# stepperDriver.net
KiCad netlist of a schematic drawn in Altium Designer
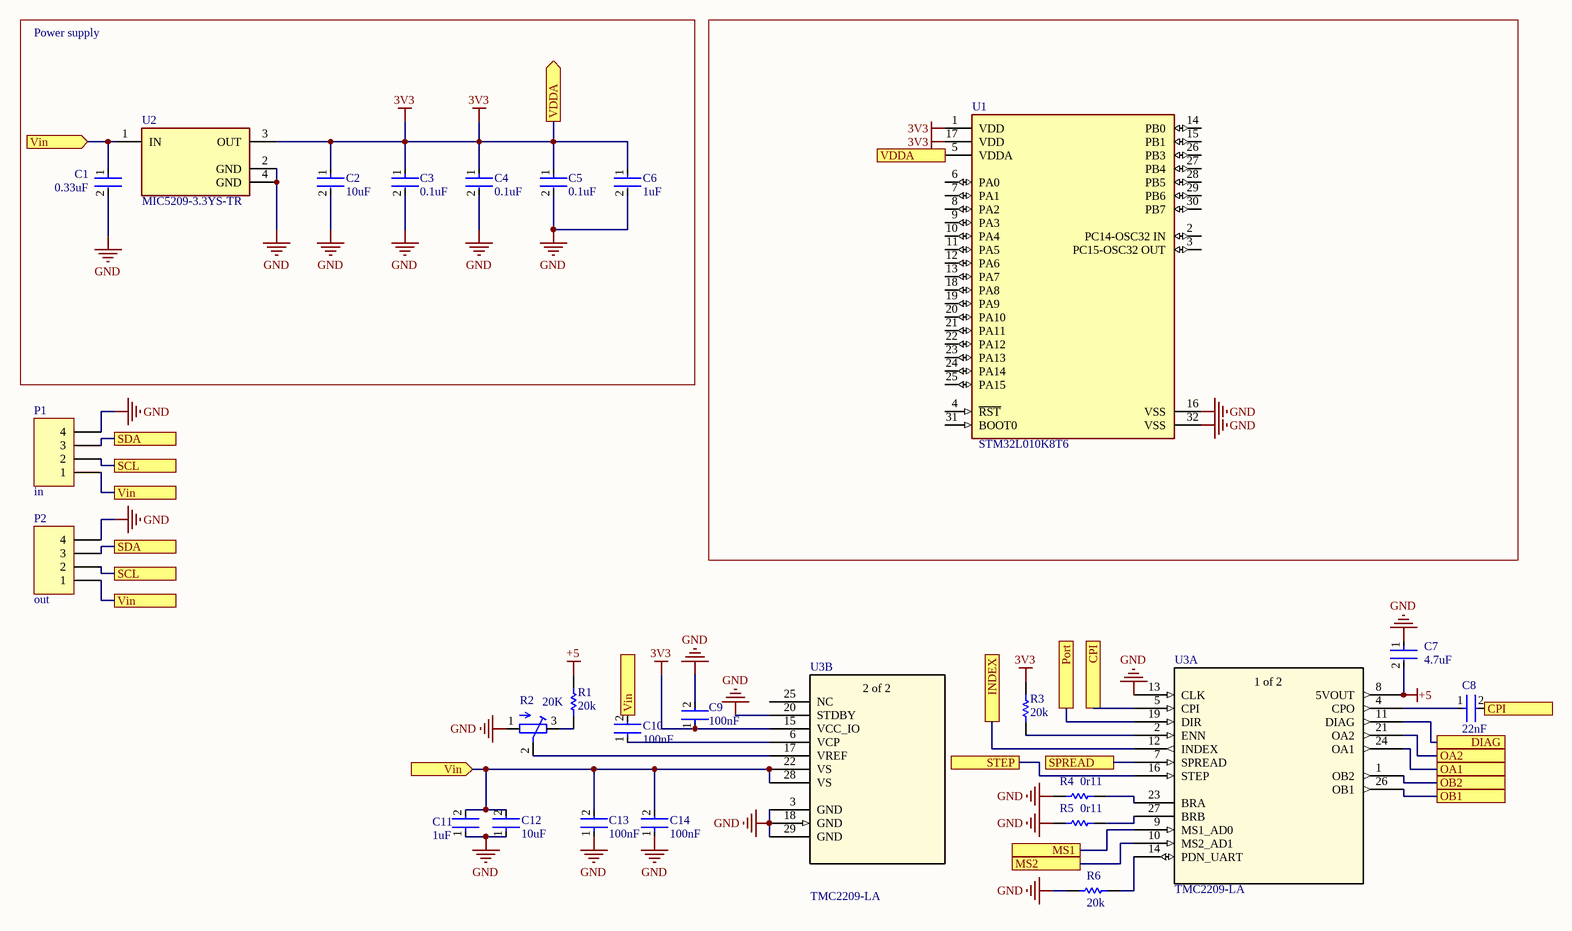
[diagram p0: stepperDriver.SchDoc]

(export (version "E")
  (design (tool "Eeschema 10.0.6"))
  (components
    (comp (ref "C1")
      (value "0.33uF")
      (footprint "FP-CL31-IPC_C")
      (description "Cap Ceramic 330pF 50V C0G ±5% SMD 1206 +125°C Embossed T/R")
      (fields (field (name "VOLTAGE") "50V") (field (name "TOLERANCE") "5%"))
      (libsource (lib "Altium Content Vault") (part "b4654b650e69147ec39a6b967a45e02"))
    )
    (comp (ref "C2")
      (value "10uF")
      (footprint "FP-CL31-IPC_A")
      (description "Cap Ceramic 10uF 16V X5R ±10% SMD 1206 +85°C Embossed T/R")
      (fields (field (name "VOLTAGE") "16V") (field (name "TOLERANCE") "10%"))
      (libsource (lib "Altium Content Vault") (part "b4654b650e69147ec39a6b967a45e02"))
    )
    (comp (ref "C3")
      (value "0.1uF")
      (footprint "FP-CGA5L-MFG")
      (description "CAP CER 0.1UF 50V C0G 1206")
      (fields
        (field (name "OCTOPART") "https://octopart.com/cga5l2c0g1h104j160aa-tdk-26014808")
        (field (name "MANUFACTURER") "TDK")
      )
      (libsource (lib "Altium Content Vault") (part "02cd4be3c70576c341d710602a673aa"))
    )
    (comp (ref "C4")
      (value "0.1uF")
      (footprint "FP-CGA5L-MFG")
      (description "CAP CER 0.1UF 50V C0G 1206")
      (fields
        (field (name "OCTOPART") "https://octopart.com/cga5l2c0g1h104j160aa-tdk-26014808")
        (field (name "MANUFACTURER") "TDK")
      )
      (libsource (lib "Altium Content Vault") (part "02cd4be3c70576c341d710602a673aa"))
    )
    (comp (ref "C5")
      (value "0.1uF")
      (footprint "FP-CGA5L-MFG")
      (description "CAP CER 0.1UF 50V C0G 1206")
      (fields
        (field (name "OCTOPART") "https://octopart.com/cga5l2c0g1h104j160aa-tdk-26014808")
        (field (name "MANUFACTURER") "TDK")
      )
      (libsource (lib "Altium Content Vault") (part "02cd4be3c70576c341d710602a673aa"))
    )
    (comp (ref "C6")
      (value "1uF")
      (footprint "FP-CL31-IPC_A")
      (description "Cap Ceramic 1uF 16V Y5V -20/+80% SMD 1206 +85°C Embossed T/R")
      (fields (field (name "TOLERANCE") "80%"))
      (libsource (lib "Altium Content Vault") (part "b4654b650e69147ec39a6b967a45e02"))
    )
    (comp (ref "C7")
      (value "4.7uF")
      (footprint "FP-CL21-IPC_C")
      (description "CL21 Series 0805 4.7uF 50V ±10% Tolerance X5R Multilayer Ceramic Chip Capacitor")
      (fields (field (name "TOLERANCE") "10%"))
      (libsource (lib "Altium Content Vault") (part "b4654b650e69147ec39a6b967a45e02"))
    )
    (comp (ref "C8")
      (value "22nF")
      (footprint "FP-CL31-IPC_A")
      (description "Cap Ceramic 22nF 50V X7R ±10% SMD 1206 +125°C Embossed T/R")
      (fields (field (name "TOLERANCE") "10%") (field (name "VOLTAGE") "50V"))
      (libsource (lib "Altium Content Vault") (part "b4654b650e69147ec39a6b967a45e02"))
    )
    (comp (ref "C9")
      (value "100nF")
      (footprint "FP-CL31-IPC_C")
      (description "Cap Ceramic 100nF 50V X7R ±10% SMD 1206 +125°C Embossed T/R")
      (fields (field (name "VOLTAGE") "50V") (field (name "TOLERANCE") "10%"))
      (libsource (lib "Altium Content Vault") (part "b4654b650e69147ec39a6b967a45e02"))
    )
    (comp (ref "C10")
      (value "100nF")
      (footprint "FP-CL31-IPC_C")
      (description "Cap Ceramic 100nF 50V X7R ±10% SMD 1206 +125°C Embossed T/R")
      (fields (field (name "VOLTAGE") "50V") (field (name "TOLERANCE") "10%"))
      (libsource (lib "Altium Content Vault") (part "b4654b650e69147ec39a6b967a45e02"))
    )
    (comp (ref "C11")
      (value "1uF")
      (footprint "FP-CL31-IPC_A")
      (description "Cap Ceramic 1uF 16V Y5V -20/+80% SMD 1206 +85°C Embossed T/R")
      (fields (field (name "TOLERANCE") "80%"))
      (libsource (lib "Altium Content Vault") (part "b4654b650e69147ec39a6b967a45e02"))
    )
    (comp (ref "C12")
      (value "10uF")
      (footprint "FP-CL31-IPC_C")
      (description "CAP CER 10UF 50V X5R 1206")
      (fields (field (name "TOLERANCE") "10%") (field (name "MANUFACTURER") "Samsung"))
      (libsource (lib "Altium Content Vault") (part "11868f565c42a9108669ba33697ecf6"))
    )
    (comp (ref "C13")
      (value "100nF")
      (footprint "FP-CL31-IPC_C")
      (description "Cap Ceramic 100nF 50V X7R ±10% SMD 1206 +125°C Embossed T/R")
      (fields (field (name "VOLTAGE") "50V") (field (name "TOLERANCE") "10%"))
      (libsource (lib "Altium Content Vault") (part "b4654b650e69147ec39a6b967a45e02"))
    )
    (comp (ref "C14")
      (value "100nF")
      (footprint "FP-CL31-IPC_C")
      (description "Cap Ceramic 100nF 50V X7R ±10% SMD 1206 +125°C Embossed T/R")
      (fields (field (name "VOLTAGE") "50V") (field (name "TOLERANCE") "10%"))
      (libsource (lib "Altium Content Vault") (part "b4654b650e69147ec39a6b967a45e02"))
    )
    (comp (ref "P1")
      (value "in")
      (footprint "HDR1X4H")
      (description "Header, 4-Pin, Right Angle")
      (fields (field (name "PUBLISHER") "Altium Limited"))
      (libsource (lib "Miscellaneous Connectors") (part "Header 4H"))
    )
    (comp (ref "P2")
      (value "out")
      (footprint "HDR1X4H")
      (description "Header, 4-Pin, Right Angle")
      (fields (field (name "PUBLISHER") "Altium Limited"))
      (libsource (lib "Miscellaneous Connectors") (part "Header 4H"))
    )
    (comp (ref "R1")
      (value "20k")
      (footprint "RESC3216X70X50LL05T20")
      (fields (field (name "MANUFACTURER") "Panasonic") (field (name "PART NUMBER") "ERJ-8GEYJ203V"))
      (libsource (lib "Altium Content Vault") (part "RES"))
    )
    (comp (ref "R2")
      (value "20K")
      (footprint "RTRIMTS53YJ")
      (fields (field (name "MF") "{'manufacturer': u'Vishay Sfernice'}") (field (name "MP") "TS53YJ"))
      (libsource (lib "SnapEDA_Library") (part "TS53YJ"))
    )
    (comp (ref "R3")
      (value "20k")
      (footprint "RESC3216X70X50LL05T20")
      (fields (field (name "MANUFACTURER") "Panasonic") (field (name "PART NUMBER") "ERJ-8GEYJ203V"))
      (libsource (lib "Altium Content Vault") (part "RES"))
    )
    (comp (ref "R4")
      (value "0r11")
      (footprint "RESC3216X70X50LL05T20")
      (fields (field (name "MANUFACTURER") "Panasonic") (field (name "PART NUMBER") "ERJ8CWFR011V"))
      (libsource (lib "Altium Content Vault") (part "RES"))
    )
    (comp (ref "R5")
      (value "0r11")
      (footprint "RESC3216X70X50LL05T20")
      (fields (field (name "MANUFACTURER") "Panasonic") (field (name "PART NUMBER") "ERJ8CWFR011V"))
      (libsource (lib "Altium Content Vault") (part "RES"))
    )
    (comp (ref "R6")
      (value "20k")
      (footprint "RESC3216X70X50LL05T20")
      (fields (field (name "MANUFACTURER") "Panasonic") (field (name "PART NUMBER") "ERJ-8GEYJ203V"))
      (libsource (lib "Altium Content Vault") (part "RES"))
    )
    (comp (ref "U1")
      (value "STM32L010K8T6")
      (footprint "FP-LQFP32-5V-MFG")
      (description "16/32-BITS MICROS")
      (fields
        (field (name "MANUFACTURER") "STMicroelectronics")
        (field (name "OCTOPART") "https://octopart.com/stm32l010k8t6-stmicroelectronics-96493834")
      )
      (libsource (lib "Altium Content Vault") (part "a17147993c2de608bb45268daa9145e"))
    )
    (comp (ref "U2")
      (value "MIC5209-3.3YS-TR")
      (footprint "FP-SOT223-3LD-PL-1-MFG")
      (description "IC REG LINEAR 3.3V 500MA SOT223")
      (libsource (lib "Altium Content Vault") (part "c31ed432f589313beb2aec2175fc138"))
    )
    (comp (ref "U3")
      (value "TMC2209-LA")
      (footprint "QFN28_5X5_TRI")
      (description "No Description Available")
      (fields (field (name "COPYRIGHT") "Copyright (C) 2022 Ultra Librarian. All rights reserved."))
      (libsource (lib "TMC2209-LA") (part "TMC2209-LA"))
    )
  )
  (nets
    (net (code "1") (name "+5") (class "Default")
      (node (ref "C7") (pin "2") (pinfunction "2_2") (pintype "passive"))
      (node (ref "R1") (pin "2") (pinfunction "2_2") (pintype "passive"))
      (node (ref "U3") (pin "8") (pinfunction "5VOUT_8") (pintype "output"))
    )
    (net (code "2") (name "/CPI") (class "Default")
      (node (ref "C8") (pin "2") (pinfunction "2_2") (pintype "passive"))
      (node (ref "U3") (pin "5") (pinfunction "CPI_5") (pintype "input"))
    )
    (net (code "3") (name "/DIAG") (class "Default")
      (node (ref "U3") (pin "11") (pinfunction "DIAG_11") (pintype "output"))
    )
    (net (code "4") (name "/INDEX") (class "Default")
      (node (ref "U3") (pin "12") (pinfunction "INDEX_12") (pintype "output"))
    )
    (net (code "5") (name "/MS1") (class "Default")
      (node (ref "U3") (pin "9") (pinfunction "MS1_AD0_9") (pintype "input"))
    )
    (net (code "6") (name "/MS2") (class "Default")
      (node (ref "U3") (pin "10") (pinfunction "MS2_AD1_10") (pintype "input"))
    )
    (net (code "7") (name "/OA1") (class "Default")
      (node (ref "U3") (pin "24") (pinfunction "OA1_24") (pintype "output"))
    )
    (net (code "8") (name "/OA2") (class "Default")
      (node (ref "U3") (pin "21") (pinfunction "OA2_21") (pintype "output"))
    )
    (net (code "9") (name "/OB1") (class "Default")
      (node (ref "U3") (pin "26") (pinfunction "OB1_26") (pintype "output"))
    )
    (net (code "10") (name "/OB2") (class "Default")
      (node (ref "U3") (pin "1") (pinfunction "OB2_1") (pintype "output"))
    )
    (net (code "11") (name "/Port") (class "Default")
      (node (ref "U3") (pin "19") (pinfunction "DIR_19") (pintype "input"))
    )
    (net (code "12") (name "/SCL") (class "Default")
      (node (ref "P1") (pin "2") (pinfunction "2_2") (pintype "passive"))
      (node (ref "P2") (pin "2") (pinfunction "2_2") (pintype "passive"))
    )
    (net (code "13") (name "/SDA") (class "Default")
      (node (ref "P1") (pin "3") (pinfunction "3_3") (pintype "passive"))
      (node (ref "P2") (pin "3") (pinfunction "3_3") (pintype "passive"))
    )
    (net (code "14") (name "/SPREAD") (class "Default")
      (node (ref "U3") (pin "7") (pinfunction "SPREAD_7") (pintype "input"))
    )
    (net (code "15") (name "/STEP") (class "Default")
      (node (ref "U3") (pin "16") (pinfunction "STEP_16") (pintype "input"))
    )
    (net (code "16") (name "/Vin") (class "Default")
      (node (ref "C1") (pin "1") (pinfunction "1_1") (pintype "passive"))
      (node (ref "C10") (pin "2") (pinfunction "2_2") (pintype "passive"))
      (node (ref "C11") (pin "2") (pinfunction "2_2") (pintype "passive"))
      (node (ref "C12") (pin "2") (pinfunction "2_2") (pintype "passive"))
      (node (ref "C13") (pin "2") (pinfunction "2_2") (pintype "passive"))
      (node (ref "C14") (pin "2") (pinfunction "2_2") (pintype "passive"))
      (node (ref "P1") (pin "1") (pinfunction "1_1") (pintype "passive"))
      (node (ref "P2") (pin "1") (pinfunction "1_1") (pintype "passive"))
      (node (ref "U2") (pin "1") (pinfunction "IN_1") (pintype "power_in"))
      (node (ref "U3") (pin "22") (pinfunction "VS_22") (pintype "power_in"))
      (node (ref "U3") (pin "28") (pinfunction "VS_28") (pintype "power_in"))
    )
    (net (code "17") (name "3V3") (class "Default")
      (node (ref "C2") (pin "1") (pinfunction "1_1") (pintype "passive"))
      (node (ref "C3") (pin "1") (pinfunction "1_1") (pintype "passive"))
      (node (ref "C4") (pin "1") (pinfunction "1_1") (pintype "passive"))
      (node (ref "C5") (pin "1") (pinfunction "1_1") (pintype "passive"))
      (node (ref "C6") (pin "1") (pinfunction "1_1") (pintype "passive"))
      (node (ref "C9") (pin "1") (pinfunction "1_1") (pintype "passive"))
      (node (ref "R3") (pin "1") (pinfunction "1_1") (pintype "passive"))
      (node (ref "U1") (pin "1") (pinfunction "VDD_1") (pintype "power_in"))
      (node (ref "U1") (pin "17") (pinfunction "VDD_17") (pintype "power_in"))
      (node (ref "U1") (pin "5") (pinfunction "VDDA_5") (pintype "power_in"))
      (node (ref "U2") (pin "3") (pinfunction "OUT_3") (pintype "power_in"))
      (node (ref "U3") (pin "15") (pinfunction "VCC_IO_15") (pintype "power_in"))
    )
    (net (code "18") (name "GND") (class "Default")
      (node (ref "C1") (pin "2") (pinfunction "2_2") (pintype "passive"))
      (node (ref "C11") (pin "1") (pinfunction "1_1") (pintype "passive"))
      (node (ref "C12") (pin "1") (pinfunction "1_1") (pintype "passive"))
      (node (ref "C13") (pin "1") (pinfunction "1_1") (pintype "passive"))
      (node (ref "C14") (pin "1") (pinfunction "1_1") (pintype "passive"))
      (node (ref "C2") (pin "2") (pinfunction "2_2") (pintype "passive"))
      (node (ref "C3") (pin "2") (pinfunction "2_2") (pintype "passive"))
      (node (ref "C4") (pin "2") (pinfunction "2_2") (pintype "passive"))
      (node (ref "C5") (pin "2") (pinfunction "2_2") (pintype "passive"))
      (node (ref "C6") (pin "2") (pinfunction "2_2") (pintype "passive"))
      (node (ref "C7") (pin "1") (pinfunction "1_1") (pintype "passive"))
      (node (ref "C9") (pin "2") (pinfunction "2_2") (pintype "passive"))
      (node (ref "P1") (pin "4") (pinfunction "4_4") (pintype "passive"))
      (node (ref "P2") (pin "4") (pinfunction "4_4") (pintype "passive"))
      (node (ref "R2") (pin "1") (pinfunction "A_1") (pintype "passive"))
      (node (ref "R4") (pin "1") (pinfunction "1_1") (pintype "passive"))
      (node (ref "R5") (pin "1") (pinfunction "1_1") (pintype "passive"))
      (node (ref "R6") (pin "1") (pinfunction "1_1") (pintype "passive"))
      (node (ref "U1") (pin "16") (pinfunction "VSS_16") (pintype "power_in"))
      (node (ref "U1") (pin "32") (pinfunction "VSS_32") (pintype "power_in"))
      (node (ref "U2") (pin "2") (pinfunction "GND_2") (pintype "power_in"))
      (node (ref "U2") (pin "4") (pinfunction "GND_4") (pintype "power_in"))
      (node (ref "U3") (pin "13") (pinfunction "CLK_13") (pintype "input"))
      (node (ref "U3") (pin "18") (pinfunction "GND_18") (pintype "input"))
      (node (ref "U3") (pin "20") (pinfunction "STDBY_20") (pintype "power_in"))
      (node (ref "U3") (pin "29") (pinfunction "GND_29") (pintype "passive"))
      (node (ref "U3") (pin "3") (pinfunction "GND_3") (pintype "passive"))
    )
    (net (code "19") (name "Net-(R2-E)") (class "Default")
      (node (ref "R1") (pin "1") (pinfunction "1_1") (pintype "passive"))
      (node (ref "R2") (pin "3") (pinfunction "E_3") (pintype "passive"))
    )
    (net (code "20") (name "Net-(R2-S)") (class "Default")
      (node (ref "R2") (pin "2") (pinfunction "S_2") (pintype "passive"))
      (node (ref "U3") (pin "17") (pinfunction "VREF_17") (pintype "passive"))
    )
    (net (code "21") (name "Net-(U3A-BRA)") (class "Default")
      (node (ref "R4") (pin "2") (pinfunction "2_2") (pintype "passive"))
      (node (ref "U3") (pin "23") (pinfunction "BRA_23") (pintype "passive"))
    )
    (net (code "22") (name "Net-(U3A-BRB)") (class "Default")
      (node (ref "R5") (pin "2") (pinfunction "2_2") (pintype "passive"))
      (node (ref "U3") (pin "27") (pinfunction "BRB_27") (pintype "passive"))
    )
    (net (code "23") (name "Net-(U3A-CPO)") (class "Default")
      (node (ref "C8") (pin "1") (pinfunction "1_1") (pintype "passive"))
      (node (ref "U3") (pin "4") (pinfunction "CPO_4") (pintype "output"))
    )
    (net (code "24") (name "Net-(U3A-ENN)") (class "Default")
      (node (ref "R3") (pin "2") (pinfunction "2_2") (pintype "passive"))
      (node (ref "U3") (pin "2") (pinfunction "ENN_2") (pintype "input"))
    )
    (net (code "25") (name "Net-(U3A-PDN_UART)") (class "Default")
      (node (ref "R6") (pin "2") (pinfunction "2_2") (pintype "passive"))
      (node (ref "U3") (pin "14") (pinfunction "PDN_UART_14") (pintype "bidirectional"))
    )
    (net (code "26") (name "Net-(U3B-VCP)") (class "Default")
      (node (ref "C10") (pin "1") (pinfunction "1_1") (pintype "passive"))
      (node (ref "U3") (pin "6") (pinfunction "VCP_6") (pintype "power_in"))
    )
    (net (code "27") (name "unconnected-(U1-BOOT0-Pad31)") (class "Default")
      (node (ref "U1") (pin "31") (pinfunction "BOOT0_31") (pintype "input"))
    )
    (net (code "28") (name "unconnected-(U1-PA0-Pad6)") (class "Default")
      (node (ref "U1") (pin "6") (pinfunction "PA0_6") (pintype "bidirectional"))
    )
    (net (code "29") (name "unconnected-(U1-PA1-Pad7)") (class "Default")
      (node (ref "U1") (pin "7") (pinfunction "PA1_7") (pintype "bidirectional"))
    )
    (net (code "30") (name "unconnected-(U1-PA2-Pad8)") (class "Default")
      (node (ref "U1") (pin "8") (pinfunction "PA2_8") (pintype "bidirectional"))
    )
    (net (code "31") (name "unconnected-(U1-PA3-Pad9)") (class "Default")
      (node (ref "U1") (pin "9") (pinfunction "PA3_9") (pintype "bidirectional"))
    )
    (net (code "32") (name "unconnected-(U1-PA4-Pad10)") (class "Default")
      (node (ref "U1") (pin "10") (pinfunction "PA4_10") (pintype "bidirectional"))
    )
    (net (code "33") (name "unconnected-(U1-PA5-Pad11)") (class "Default")
      (node (ref "U1") (pin "11") (pinfunction "PA5_11") (pintype "bidirectional"))
    )
    (net (code "34") (name "unconnected-(U1-PA6-Pad12)") (class "Default")
      (node (ref "U1") (pin "12") (pinfunction "PA6_12") (pintype "bidirectional"))
    )
    (net (code "35") (name "unconnected-(U1-PA7-Pad13)") (class "Default")
      (node (ref "U1") (pin "13") (pinfunction "PA7_13") (pintype "bidirectional"))
    )
    (net (code "36") (name "unconnected-(U1-PA8-Pad18)") (class "Default")
      (node (ref "U1") (pin "18") (pinfunction "PA8_18") (pintype "bidirectional"))
    )
    (net (code "37") (name "unconnected-(U1-PA9-Pad19)") (class "Default")
      (node (ref "U1") (pin "19") (pinfunction "PA9_19") (pintype "bidirectional"))
    )
    (net (code "38") (name "unconnected-(U1-PA10-Pad20)") (class "Default")
      (node (ref "U1") (pin "20") (pinfunction "PA10_20") (pintype "bidirectional"))
    )
    (net (code "39") (name "unconnected-(U1-PA11-Pad21)") (class "Default")
      (node (ref "U1") (pin "21") (pinfunction "PA11_21") (pintype "bidirectional"))
    )
    (net (code "40") (name "unconnected-(U1-PA12-Pad22)") (class "Default")
      (node (ref "U1") (pin "22") (pinfunction "PA12_22") (pintype "bidirectional"))
    )
    (net (code "41") (name "unconnected-(U1-PA13-Pad23)") (class "Default")
      (node (ref "U1") (pin "23") (pinfunction "PA13_23") (pintype "bidirectional"))
    )
    (net (code "42") (name "unconnected-(U1-PA14-Pad24)") (class "Default")
      (node (ref "U1") (pin "24") (pinfunction "PA14_24") (pintype "bidirectional"))
    )
    (net (code "43") (name "unconnected-(U1-PA15-Pad25)") (class "Default")
      (node (ref "U1") (pin "25") (pinfunction "PA15_25") (pintype "bidirectional"))
    )
    (net (code "44") (name "unconnected-(U1-PB0-Pad14)") (class "Default")
      (node (ref "U1") (pin "14") (pinfunction "PB0_14") (pintype "bidirectional"))
    )
    (net (code "45") (name "unconnected-(U1-PB1-Pad15)") (class "Default")
      (node (ref "U1") (pin "15") (pinfunction "PB1_15") (pintype "bidirectional"))
    )
    (net (code "46") (name "unconnected-(U1-PB3-Pad26)") (class "Default")
      (node (ref "U1") (pin "26") (pinfunction "PB3_26") (pintype "bidirectional"))
    )
    (net (code "47") (name "unconnected-(U1-PB4-Pad27)") (class "Default")
      (node (ref "U1") (pin "27") (pinfunction "PB4_27") (pintype "bidirectional"))
    )
    (net (code "48") (name "unconnected-(U1-PB5-Pad28)") (class "Default")
      (node (ref "U1") (pin "28") (pinfunction "PB5_28") (pintype "bidirectional"))
    )
    (net (code "49") (name "unconnected-(U1-PB6-Pad29)") (class "Default")
      (node (ref "U1") (pin "29") (pinfunction "PB6_29") (pintype "bidirectional"))
    )
    (net (code "50") (name "unconnected-(U1-PB7-Pad30)") (class "Default")
      (node (ref "U1") (pin "30") (pinfunction "PB7_30") (pintype "bidirectional"))
    )
    (net (code "51") (name "unconnected-(U1-PC14-OSC32_IN-Pad2)") (class "Default")
      (node (ref "U1") (pin "2") (pinfunction "PC14-OSC32_IN_2") (pintype "bidirectional"))
    )
    (net (code "52") (name "unconnected-(U1-PC15-OSC32_OUT-Pad3)") (class "Default")
      (node (ref "U1") (pin "3") (pinfunction "PC15-OSC32_OUT_3") (pintype "bidirectional"))
    )
    (net (code "53") (name "unconnected-(U1-~{RST}-Pad4)") (class "Default")
      (node (ref "U1") (pin "4") (pinfunction "~{RST}_4") (pintype "input"))
    )
    (net (code "54") (name "unconnected-(U3B-NC-Pad25)") (class "Default")
      (node (ref "U3") (pin "25") (pinfunction "NC_25") (pintype "passive"))
    )
  )
)
